# 6_-_POWER.net
KiCad netlist of a schematic drawn in Altium Designer
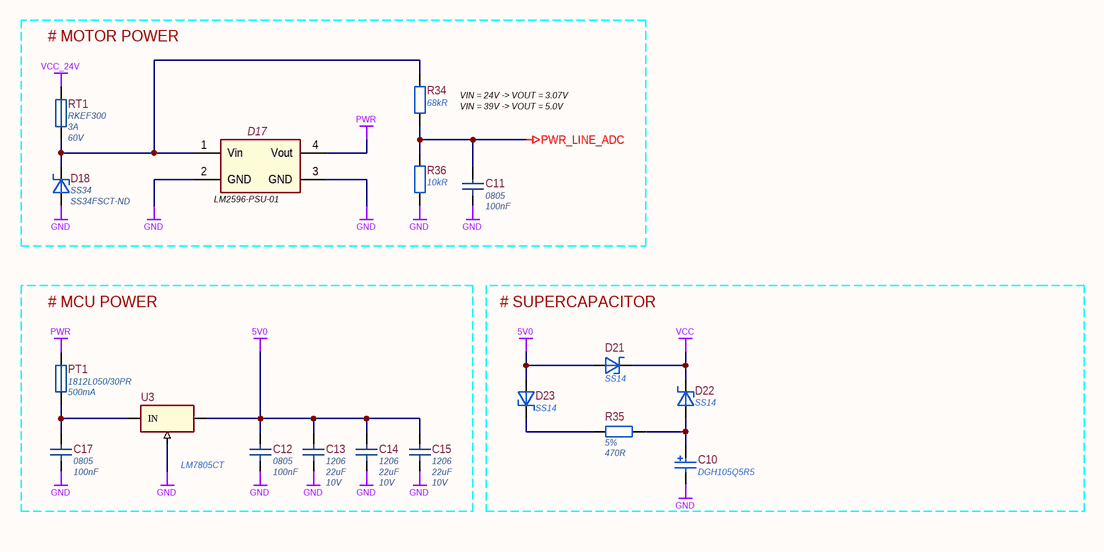
[diagram p0: [6] - POWER.SchDoc]

(export (version "E")
  (design (tool "Eeschema 10.0.6"))
  (components
    (comp (ref "C10")
      (value "DGH105Q5R5")
      (footprint "DGH105Q5R5")
      (description "CAPACITOR 1F -10% +30% 5.5V TH")
      (libsource (lib "Electrolytic Capacitors") (part "DGH105Q5R5"))
    )
    (comp (ref "C11")
      (value "AC0805KRX7R9BB104")
      (footprint "CH0805C")
      (description "0.10µF 50V Ceramic Capacitor X7R 0805 (2012 Metric) 0.079\" L x 0.049\" W (2.00mm x 1.25mm)")
      (fields
        (field (name "CASE/PACKAGE") "0805")
        (field (name "CAPACITANCE") "100nF")
        (field (name "TOLERANCE") "10%")
      )
      (libsource (lib "Chip Capacitors") (part "AC0805KRX7R9BB104"))
    )
    (comp (ref "C12")
      (value "AC0805KRX7R9BB104")
      (footprint "CH0805C")
      (description "0.10µF 50V Ceramic Capacitor X7R 0805 (2012 Metric) 0.079\" L x 0.049\" W (2.00mm x 1.25mm)")
      (fields
        (field (name "CASE/PACKAGE") "0805")
        (field (name "CAPACITANCE") "100nF")
        (field (name "TOLERANCE") "10%")
      )
      (libsource (lib "Chip Capacitors") (part "AC0805KRX7R9BB104"))
    )
    (comp (ref "C13")
      (value "CC1206KKX5R6BB226")
      (footprint "CH1206C")
      (description "Cap Ceramic 22uF 10V X5R 10% SMD 1206 85C Blister T/R")
      (fields
        (field (name "CASE/PACKAGE") "1206")
        (field (name "CAPACITANCE") "22uF")
        (field (name "TOLERANCE") "10%")
        (field (name "VOLTAGE RATING") "10V")
      )
      (libsource (lib "Chip Capacitors") (part "CC1206KKX5R6BB226"))
    )
    (comp (ref "C14")
      (value "CC1206KKX5R6BB226")
      (footprint "CH1206C")
      (description "Cap Ceramic 22uF 10V X5R 10% SMD 1206 85C Blister T/R")
      (fields
        (field (name "CASE/PACKAGE") "1206")
        (field (name "CAPACITANCE") "22uF")
        (field (name "TOLERANCE") "10%")
        (field (name "VOLTAGE RATING") "10V")
      )
      (libsource (lib "Chip Capacitors") (part "CC1206KKX5R6BB226"))
    )
    (comp (ref "C15")
      (value "CC1206KKX5R6BB226")
      (footprint "CH1206C")
      (description "Cap Ceramic 22uF 10V X5R 10% SMD 1206 85C Blister T/R")
      (fields
        (field (name "CASE/PACKAGE") "1206")
        (field (name "CAPACITANCE") "22uF")
        (field (name "TOLERANCE") "10%")
        (field (name "VOLTAGE RATING") "10V")
      )
      (libsource (lib "Chip Capacitors") (part "CC1206KKX5R6BB226"))
    )
    (comp (ref "C17")
      (value "AC0805KRX7R9BB104")
      (footprint "CH0805C")
      (description "0.10µF 50V Ceramic Capacitor X7R 0805 (2012 Metric) 0.079\" L x 0.049\" W (2.00mm x 1.25mm)")
      (fields
        (field (name "CASE/PACKAGE") "0805")
        (field (name "CAPACITANCE") "100nF")
        (field (name "TOLERANCE") "10%")
      )
      (libsource (lib "Chip Capacitors") (part "AC0805KRX7R9BB104"))
    )
    (comp (ref "D17")
      (value "LM2596-PSU-01")
      (footprint "LM2596-PSU-01")
      (description "LM2596 DC-DC Step Down Adjustable PSU Module")
      (libsource (lib "Modules") (part "LM2596-PSU-01"))
    )
    (comp (ref "D18")
      (value "SS34")
      (footprint "SMB")
      (description "DIODE SCHOTTKY 40V 3A SMC")
      (fields (field (name "VOLTAGE") "40V") (field (name "SUPPLIER PART NUMBER 1") "SS34FSCT-ND"))
      (libsource (lib "Diodes") (part "SS34"))
    )
    (comp (ref "D21")
      (value "SS14")
      (footprint "SMA")
      (description "ON SEMICONDUCTOR - SS14 - DIODE, SCHOTTKY, 1A, 40V, DO-214AC-2")
      (fields (field (name "VOLTAGE") "40V"))
      (libsource (lib "Diodes") (part "SS14"))
    )
    (comp (ref "D22")
      (value "SS14")
      (footprint "SMA")
      (description "ON SEMICONDUCTOR - SS14 - DIODE, SCHOTTKY, 1A, 40V, DO-214AC-2")
      (fields (field (name "VOLTAGE") "40V"))
      (libsource (lib "Diodes") (part "SS14"))
    )
    (comp (ref "D23")
      (value "SS14")
      (footprint "SMA")
      (description "ON SEMICONDUCTOR - SS14 - DIODE, SCHOTTKY, 1A, 40V, DO-214AC-2")
      (fields (field (name "VOLTAGE") "40V"))
      (libsource (lib "Diodes") (part "SS14"))
    )
    (comp (ref "PT1")
      (value "1812L050/30PR")
      (footprint "CH1812F")
      (description "PTC RESET FUSE 30V 500MA 1812")
      (fields (field (name "HOLD CURRENT") "500mA"))
      (libsource (lib "Fuses") (part "1812L050/30PR"))
    )
    (comp (ref "R34")
      (value "RC0805JR-0768KL")
      (footprint "CH0805R")
      (description "Res Thick Film 0805 68K Ohm 5% 0.125W(1/8W) ±100ppm/C Epoxy Pad SMD T/R")
      (fields (field (name "RESISTANCE") "68kR") (field (name "TOLERANCE") "5%"))
      (libsource (lib "Chip Resistors") (part "RC0805JR-0768KL"))
    )
    (comp (ref "R35")
      (value "RC0805JR-07470RL")
      (footprint "CH0805R")
      (description "RES SMD 470 OHM 5% 1/8W 0805")
      (fields (field (name "TOLERANCE") "5%") (field (name "RESISTANCE") "470R"))
      (libsource (lib "Chip Resistors") (part "RC0805JR-07470RL"))
    )
    (comp (ref "R36")
      (value "RC0805JR-0710KL")
      (footprint "CH0805R")
      (description "RES SMD 10K OHM 5% 1/8W 0805")
      (fields (field (name "TOLERANCE") "5%") (field (name "RESISTANCE") "10kR"))
      (libsource (lib "Chip Resistors") (part "RC0805JR-0710KL"))
    )
    (comp (ref "RT1")
      (value "RKEF300")
      (footprint "RKEF300")
      (description "TE Connectivity 3A Radial Leaded PCB Mount Resettable Fuse, 60 V")
      (fields (field (name "HOLD CURRENT") "3A") (field (name "VOLTAGE RATING") "60V"))
      (libsource (lib "Fuses") (part "RKEF300"))
    )
    (comp (ref "U3")
      (value "LM7805CT")
      (footprint "TO-220F")
      (libsource (lib "Voltage Regulators") (part "LM7805CT"))
    )
  )
  (nets
    (net (code "1") (name "5V0") (class "Default")
      (node (ref "C12") (pin "1") (pinfunction "1_1") (pintype "passive"))
      (node (ref "C13") (pin "1") (pinfunction "1_1") (pintype "passive"))
      (node (ref "C14") (pin "1") (pinfunction "1_1") (pintype "passive"))
      (node (ref "C15") (pin "1") (pinfunction "1_1") (pintype "passive"))
      (node (ref "D21") (pin "1") (pinfunction "A_1") (pintype "passive"))
      (node (ref "D23") (pin "1") (pinfunction "A_1") (pintype "passive"))
      (node (ref "U3") (pin "3") (pinfunction "OUT_3") (pintype "power_in"))
    )
    (net (code "2") (name "GND") (class "Default")
      (node (ref "C10") (pin "2") (pinfunction "2_2") (pintype "passive"))
      (node (ref "C11") (pin "2") (pinfunction "2_2") (pintype "passive"))
      (node (ref "C12") (pin "2") (pinfunction "2_2") (pintype "passive"))
      (node (ref "C13") (pin "2") (pinfunction "2_2") (pintype "passive"))
      (node (ref "C14") (pin "2") (pinfunction "2_2") (pintype "passive"))
      (node (ref "C15") (pin "2") (pinfunction "2_2") (pintype "passive"))
      (node (ref "C17") (pin "2") (pinfunction "2_2") (pintype "passive"))
      (node (ref "D17") (pin "2") (pinfunction "GND_2") (pintype "power_in"))
      (node (ref "D17") (pin "3") (pinfunction "GND_3") (pintype "power_in"))
      (node (ref "D18") (pin "1") (pinfunction "A_1") (pintype "passive"))
      (node (ref "R36") (pin "1") (pinfunction "1_1") (pintype "passive"))
      (node (ref "U3") (pin "2") (pinfunction "GND_2") (pintype "input"))
    )
    (net (code "3") (name "Net-(D17-Vin)") (class "Default")
      (node (ref "D17") (pin "1") (pinfunction "Vin_1") (pintype "power_in"))
      (node (ref "D18") (pin "2") (pinfunction "K_2") (pintype "passive"))
      (node (ref "R34") (pin "2") (pinfunction "2_2") (pintype "passive"))
      (node (ref "RT1") (pin "2") (pinfunction "2_2") (pintype "passive"))
    )
    (net (code "4") (name "Net-(D22-A)") (class "Default")
      (node (ref "C10") (pin "1") (pinfunction "1_1") (pintype "passive"))
      (node (ref "D22") (pin "1") (pinfunction "A_1") (pintype "passive"))
      (node (ref "R35") (pin "1") (pinfunction "1_1") (pintype "passive"))
    )
    (net (code "5") (name "Net-(D23-K)") (class "Default")
      (node (ref "D23") (pin "2") (pinfunction "K_2") (pintype "passive"))
      (node (ref "R35") (pin "2") (pinfunction "2_2") (pintype "passive"))
    )
    (net (code "6") (name "Net-(U3-IN)") (class "Default")
      (node (ref "C17") (pin "1") (pinfunction "1_1") (pintype "passive"))
      (node (ref "PT1") (pin "2") (pinfunction "2_2") (pintype "passive"))
      (node (ref "U3") (pin "1") (pinfunction "IN_1") (pintype "power_in"))
    )
    (net (code "7") (name "PWR") (class "Default")
      (node (ref "D17") (pin "4") (pinfunction "Vout_4") (pintype "power_in"))
      (node (ref "PT1") (pin "1") (pinfunction "1_1") (pintype "passive"))
    )
    (net (code "8") (name "PWR_LINE_ADC") (class "Default")
      (node (ref "C11") (pin "1") (pinfunction "1_1") (pintype "passive"))
      (node (ref "R34") (pin "1") (pinfunction "1_1") (pintype "passive"))
      (node (ref "R36") (pin "2") (pinfunction "2_2") (pintype "passive"))
    )
    (net (code "9") (name "VCC") (class "Default")
      (node (ref "D21") (pin "2") (pinfunction "K_2") (pintype "passive"))
      (node (ref "D22") (pin "2") (pinfunction "K_2") (pintype "passive"))
    )
    (net (code "10") (name "VCC_24V") (class "Default")
      (node (ref "RT1") (pin "1") (pinfunction "1_1") (pintype "passive"))
    )
  )
)
